# PPS_BUFFER.net
KiCad netlist of a schematic drawn in Altium Designer
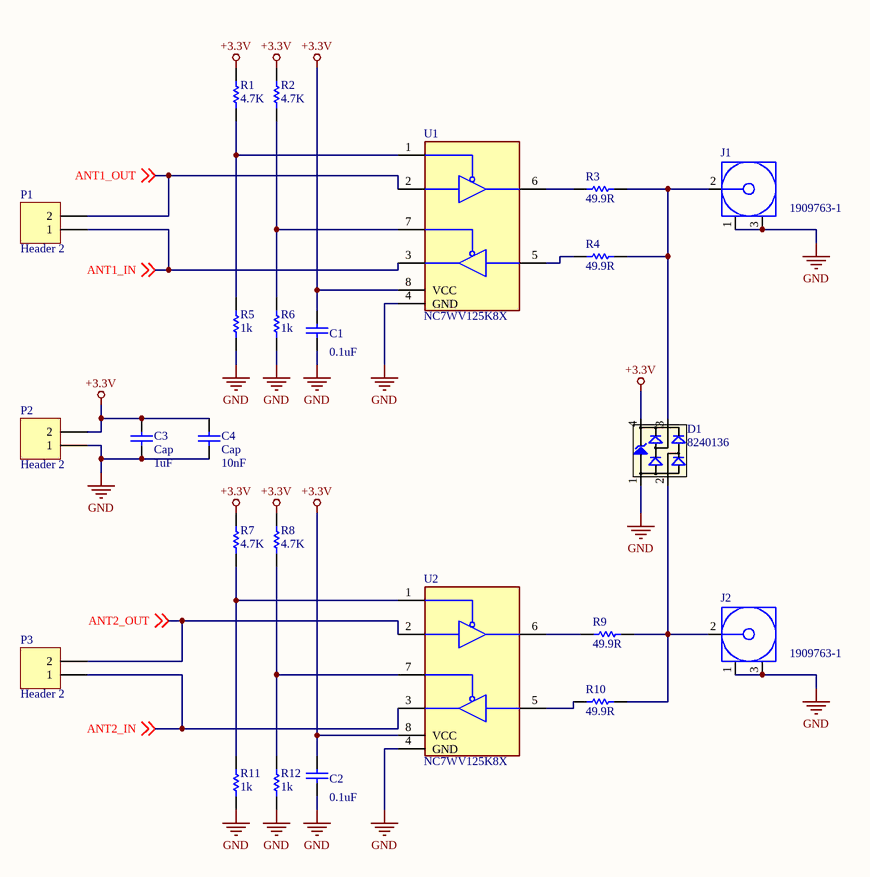
[diagram p0: PPS_BUFFER.SchDoc]

(export (version "E")
  (design (tool "Eeschema 10.0.6"))
  (components
    (comp (ref "C1")
      (value "0.1uF")
      (footprint "CAPC1608X87X45ML20T05")
      (description "C0603X104K5RACAUTO")
      (fields (field (name "MANUFACTURER") "Kemet"))
      (libsource (lib "Altium Content Vault") (part "CAP"))
    )
    (comp (ref "C2")
      (value "0.1uF")
      (footprint "CAPC1608X87X45ML20T05")
      (description "C0603X104K5RACAUTO")
      (fields (field (name "MANUFACTURER") "Kemet"))
      (libsource (lib "Altium Content Vault") (part "CAP"))
    )
    (comp (ref "C3")
      (value "Cap")
      (footprint "6-0805_L")
      (description "Capacitor")
      (fields (field (name "ALTIUM_VALUE") "1uF") (field (name "PUBLISHER") "Altium Limited"))
      (libsource (lib "Miscellaneous Devices") (part "Cap"))
    )
    (comp (ref "C4")
      (value "Cap")
      (footprint "6-0805_L")
      (description "Capacitor")
      (fields (field (name "ALTIUM_VALUE") "10nF") (field (name "PUBLISHER") "Altium Limited"))
      (libsource (lib "Miscellaneous Devices") (part "Cap"))
    )
    (comp (ref "D1")
      (value "8240136")
      (footprint "SOT143-4L")
      (description "TVS Diode WE-TVS-HS, VRWM=3.3V")
      (fields (field (name "MANUFACTURER") "Wuerth Elektronik"))
      (libsource (lib "Altium Content Vault") (part "WE-TVS-HS-4"))
    )
    (comp (ref "J1")
      (value "1909763-1")
      (footprint "TECO-1909763-1_V")
      (description "Ultra Miniature Coaxial Connector Jack, 60 V, 50 Ohm, -40 to 90 degC, RoHS, Tape and Reel")
      (fields (field (name "MANUFACTURER") "TE Connectivity"))
      (libsource (lib "Altium Content Vault") (part "CN-1P-M-RF3"))
    )
    (comp (ref "J2")
      (value "1909763-1")
      (footprint "TECO-1909763-1_V")
      (description "Ultra Miniature Coaxial Connector Jack, 60 V, 50 Ohm, -40 to 90 degC, RoHS, Tape and Reel")
      (fields (field (name "MANUFACTURER") "TE Connectivity"))
      (libsource (lib "Altium Content Vault") (part "CN-1P-M-RF3"))
    )
    (comp (ref "P1")
      (value "Header 2")
      (footprint "3.5X2.8X1.9")
      (description "Header, 2-Pin")
      (fields (field (name "PUBLISHER") "Altium Limited"))
      (libsource (lib "Miscellaneous Connectors") (part "Header 2"))
    )
    (comp (ref "P2")
      (value "Header 2")
      (footprint "3.5X2.8X1.9")
      (description "Header, 2-Pin")
      (fields (field (name "PUBLISHER") "Altium Limited"))
      (libsource (lib "Miscellaneous Connectors") (part "Header 2"))
    )
    (comp (ref "P3")
      (value "Header 2")
      (footprint "3.5X2.8X1.9")
      (description "Header, 2-Pin")
      (fields (field (name "PUBLISHER") "Altium Limited"))
      (libsource (lib "Miscellaneous Connectors") (part "Header 2"))
    )
    (comp (ref "R1")
      (value "4.7K")
      (footprint "RESC1608X55X30NL15T15")
      (fields (field (name "TOLERANCE") "5%"))
      (libsource (lib "Altium Content Vault") (part "RES-2"))
    )
    (comp (ref "R2")
      (value "4.7K")
      (footprint "RESC1608X55X30NL15T15")
      (fields (field (name "TOLERANCE") "5%"))
      (libsource (lib "Altium Content Vault") (part "RES-2"))
    )
    (comp (ref "R3")
      (value "49.9R")
      (footprint "RESC1608X55X25NL10T15")
      (libsource (lib "Altium Content Vault") (part "RES-2"))
    )
    (comp (ref "R4")
      (value "49.9R")
      (footprint "RESC1608X55X25NL10T15")
      (libsource (lib "Altium Content Vault") (part "RES-2"))
    )
    (comp (ref "R5")
      (value "1k")
      (footprint "RESC1608X55X25NL10T15")
      (libsource (lib "Altium Content Vault") (part "RES-2"))
    )
    (comp (ref "R6")
      (value "1k")
      (footprint "RESC1608X55X25NL10T15")
      (libsource (lib "Altium Content Vault") (part "RES-2"))
    )
    (comp (ref "R7")
      (value "4.7K")
      (footprint "RESC1608X55X30NL15T15")
      (fields (field (name "TOLERANCE") "5%"))
      (libsource (lib "Altium Content Vault") (part "RES-2"))
    )
    (comp (ref "R8")
      (value "4.7K")
      (footprint "RESC1608X55X30NL15T15")
      (fields (field (name "TOLERANCE") "5%"))
      (libsource (lib "Altium Content Vault") (part "RES-2"))
    )
    (comp (ref "R9")
      (value "49.9R")
      (footprint "RESC1608X55X25NL10T15")
      (libsource (lib "Altium Content Vault") (part "RES-2"))
    )
    (comp (ref "R10")
      (value "49.9R")
      (footprint "RESC1608X55X25NL10T15")
      (libsource (lib "Altium Content Vault") (part "RES-2"))
    )
    (comp (ref "R11")
      (value "1k")
      (footprint "RESC1608X55X25NL10T15")
      (libsource (lib "Altium Content Vault") (part "RES-2"))
    )
    (comp (ref "R12")
      (value "1k")
      (footprint "RESC1608X55X25NL10T15")
      (libsource (lib "Altium Content Vault") (part "RES-2"))
    )
    (comp (ref "U1")
      (value "NC7WV125K8X")
      (footprint "SOP50P310X90-8N")
      (description "Integrated Circuit")
      (fields (field (name "MOUSER PART NUMBER") "512-NC7WV125K8X"))
      (libsource (lib "SamacSys") (part "NC7WV125K8X"))
    )
    (comp (ref "U2")
      (value "NC7WV125K8X")
      (footprint "SOP50P310X90-8N")
      (description "Integrated Circuit")
      (fields (field (name "MOUSER PART NUMBER") "512-NC7WV125K8X"))
      (libsource (lib "SamacSys") (part "NC7WV125K8X"))
    )
  )
  (nets
    (net (code "1") (name "+3.3V") (class "Default")
      (node (ref "C1") (pin "1") (pinfunction "1_1") (pintype "passive"))
      (node (ref "C2") (pin "1") (pinfunction "1_1") (pintype "passive"))
      (node (ref "C3") (pin "1") (pinfunction "1_1") (pintype "passive"))
      (node (ref "C4") (pin "1") (pinfunction "1_1") (pintype "passive"))
      (node (ref "D1") (pin "4") (pinfunction "VDD_4") (pintype "passive"))
      (node (ref "P2") (pin "2") (pinfunction "2_2") (pintype "passive"))
      (node (ref "R1") (pin "2") (pinfunction "2_2") (pintype "passive"))
      (node (ref "R2") (pin "2") (pinfunction "2_2") (pintype "passive"))
      (node (ref "R7") (pin "2") (pinfunction "2_2") (pintype "passive"))
      (node (ref "R8") (pin "2") (pinfunction "2_2") (pintype "passive"))
      (node (ref "U1") (pin "8") (pinfunction "VCC_8") (pintype "passive"))
      (node (ref "U2") (pin "8") (pinfunction "VCC_8") (pintype "passive"))
    )
    (net (code "2") (name "ANT1_IN") (class "Default")
      (node (ref "P1") (pin "1") (pinfunction "1_1") (pintype "passive"))
      (node (ref "U1") (pin "3") (pintype "passive"))
    )
    (net (code "3") (name "ANT1_OUT") (class "Default")
      (node (ref "P1") (pin "2") (pinfunction "2_2") (pintype "passive"))
      (node (ref "U1") (pin "2") (pintype "passive"))
    )
    (net (code "4") (name "ANT2_IN") (class "Default")
      (node (ref "P3") (pin "1") (pinfunction "1_1") (pintype "passive"))
      (node (ref "U2") (pin "3") (pintype "passive"))
    )
    (net (code "5") (name "ANT2_OUT") (class "Default")
      (node (ref "P3") (pin "2") (pinfunction "2_2") (pintype "passive"))
      (node (ref "U2") (pin "2") (pintype "passive"))
    )
    (net (code "6") (name "GND") (class "Default")
      (node (ref "C1") (pin "2") (pinfunction "2_2") (pintype "passive"))
      (node (ref "C2") (pin "2") (pinfunction "2_2") (pintype "passive"))
      (node (ref "C3") (pin "2") (pinfunction "2_2") (pintype "passive"))
      (node (ref "C4") (pin "2") (pinfunction "2_2") (pintype "passive"))
      (node (ref "D1") (pin "1") (pinfunction "GND_1") (pintype "passive"))
      (node (ref "J1") (pin "1") (pinfunction "1_1") (pintype "passive"))
      (node (ref "J1") (pin "3") (pinfunction "3_3") (pintype "passive"))
      (node (ref "J2") (pin "1") (pinfunction "1_1") (pintype "passive"))
      (node (ref "J2") (pin "3") (pinfunction "3_3") (pintype "passive"))
      (node (ref "P2") (pin "1") (pinfunction "1_1") (pintype "passive"))
      (node (ref "R11") (pin "1") (pinfunction "1_1") (pintype "passive"))
      (node (ref "R12") (pin "1") (pinfunction "1_1") (pintype "passive"))
      (node (ref "R5") (pin "1") (pinfunction "1_1") (pintype "passive"))
      (node (ref "R6") (pin "1") (pinfunction "1_1") (pintype "passive"))
      (node (ref "U1") (pin "4") (pinfunction "GND_4") (pintype "passive"))
      (node (ref "U2") (pin "4") (pinfunction "GND_4") (pintype "passive"))
    )
    (net (code "7") (name "Net-(D1-I{slash}O1)") (class "Default")
      (node (ref "D1") (pin "2") (pinfunction "I/O1_2") (pintype "passive"))
      (node (ref "J2") (pin "2") (pinfunction "2_2") (pintype "passive"))
      (node (ref "R10") (pin "2") (pinfunction "2_2") (pintype "passive"))
      (node (ref "R9") (pin "2") (pinfunction "2_2") (pintype "passive"))
    )
    (net (code "8") (name "Net-(D1-I{slash}O2)") (class "Default")
      (node (ref "D1") (pin "3") (pinfunction "I/O2_3") (pintype "passive"))
      (node (ref "J1") (pin "2") (pinfunction "2_2") (pintype "passive"))
      (node (ref "R3") (pin "2") (pinfunction "2_2") (pintype "passive"))
      (node (ref "R4") (pin "2") (pinfunction "2_2") (pintype "passive"))
    )
    (net (code "9") (name "Net-(R1-Pad1)") (class "Default")
      (node (ref "R1") (pin "1") (pinfunction "1_1") (pintype "passive"))
      (node (ref "R5") (pin "2") (pinfunction "2_2") (pintype "passive"))
      (node (ref "U1") (pin "1") (pintype "passive"))
    )
    (net (code "10") (name "Net-(R2-Pad1)") (class "Default")
      (node (ref "R2") (pin "1") (pinfunction "1_1") (pintype "passive"))
      (node (ref "R6") (pin "2") (pinfunction "2_2") (pintype "passive"))
      (node (ref "U1") (pin "7") (pintype "passive"))
    )
    (net (code "11") (name "Net-(R3-Pad1)") (class "Default")
      (node (ref "R3") (pin "1") (pinfunction "1_1") (pintype "passive"))
      (node (ref "U1") (pin "6") (pintype "passive"))
    )
    (net (code "12") (name "Net-(R4-Pad1)") (class "Default")
      (node (ref "R4") (pin "1") (pinfunction "1_1") (pintype "passive"))
      (node (ref "U1") (pin "5") (pintype "passive"))
    )
    (net (code "13") (name "Net-(R9-Pad1)") (class "Default")
      (node (ref "R9") (pin "1") (pinfunction "1_1") (pintype "passive"))
      (node (ref "U2") (pin "6") (pintype "passive"))
    )
    (net (code "14") (name "Net-(R10-Pad1)") (class "Default")
      (node (ref "R10") (pin "1") (pinfunction "1_1") (pintype "passive"))
      (node (ref "U2") (pin "5") (pintype "passive"))
    )
    (net (code "15") (name "Net-(R11-Pad2)") (class "Default")
      (node (ref "R11") (pin "2") (pinfunction "2_2") (pintype "passive"))
      (node (ref "R7") (pin "1") (pinfunction "1_1") (pintype "passive"))
      (node (ref "U2") (pin "1") (pintype "passive"))
    )
    (net (code "16") (name "Net-(R12-Pad2)") (class "Default")
      (node (ref "R12") (pin "2") (pinfunction "2_2") (pintype "passive"))
      (node (ref "R8") (pin "1") (pinfunction "1_1") (pintype "passive"))
      (node (ref "U2") (pin "7") (pintype "passive"))
    )
  )
)
